# ignitors.net
KiCad netlist of a schematic drawn in EAGLE
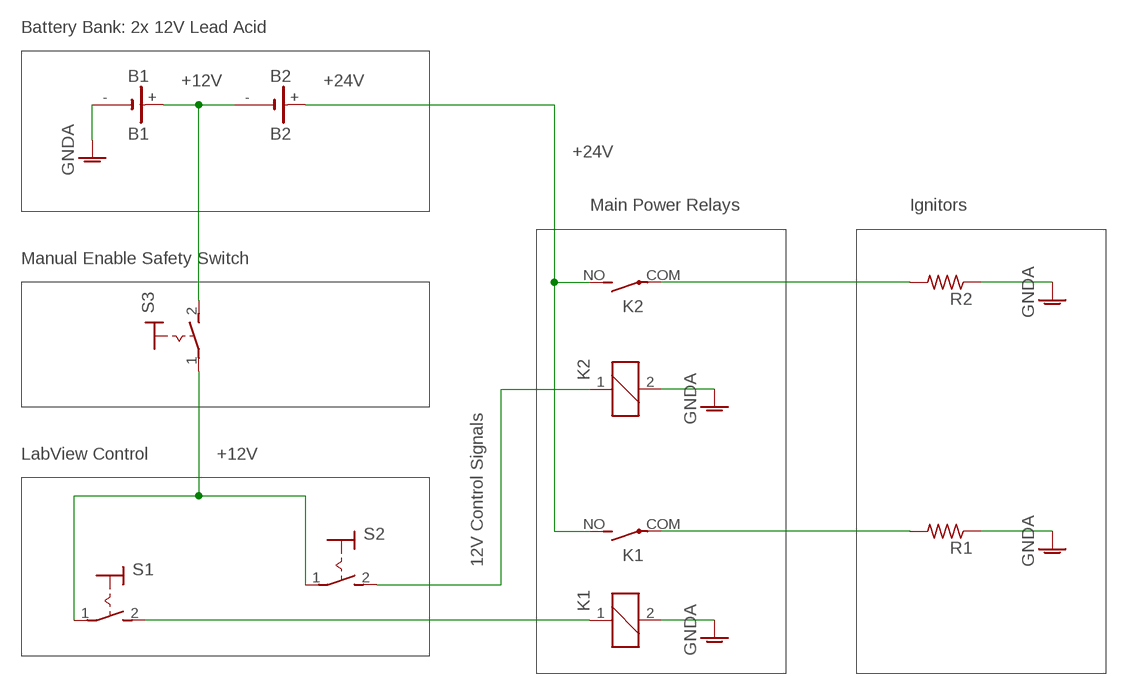
[diagram p0: schematic, sheet 1]

(export (version "E")
  (design (tool "Eeschema 10.0.6"))
  (components
    (comp (ref "B1")
      (value "B1")
      (footprint "eagle-import:SL-160AA_PT")
      (libsource (lib "eagle-import") (part "SL-160AA/PT"))
    )
    (comp (ref "B2")
      (value "B2")
      (footprint "eagle-import:SL-160AA_PT")
      (libsource (lib "eagle-import") (part "SL-160AA/PT"))
    )
    (comp (ref "K1")
      (value "APF30212A")
      (footprint "eagle-import:APF30212A")
      (libsource (lib "eagle-import") (part "APF30212A"))
    )
    (comp (ref "K2")
      (value "APF30212A")
      (footprint "eagle-import:APF30212A")
      (libsource (lib "eagle-import") (part "APF30212A"))
    )
    (comp (ref "R1")
      (value "R-US_0204/2V")
      (footprint "eagle-import:0204V")
      (libsource (lib "eagle-import") (part "R-US_0204/2V"))
    )
    (comp (ref "R2")
      (value "R-US_0204/2V")
      (footprint "eagle-import:0204V")
      (libsource (lib "eagle-import") (part "R-US_0204/2V"))
    )
    (comp (ref "S1")
      (value "MS243")
      (footprint "eagle-import:MS243")
      (libsource (lib "eagle-import") (part "MS243"))
    )
    (comp (ref "S2")
      (value "MS243")
      (footprint "eagle-import:MS243")
      (libsource (lib "eagle-import") (part "MS243"))
    )
    (comp (ref "S3")
      (value "MS243")
      (footprint "eagle-import:MS243")
      (libsource (lib "eagle-import") (part "MS243"))
    )
  )
  (nets
    (net (code "1") (name "GNDA") (class "Default")
      (node (ref "B1") (pin "-") (pinfunction "-_-") (pintype "passive"))
      (node (ref "K1") (pin "2") (pinfunction "2_2") (pintype "passive"))
      (node (ref "K2") (pin "2") (pinfunction "2_2") (pintype "passive"))
      (node (ref "R1") (pin "1") (pinfunction "1_1") (pintype "passive"))
      (node (ref "R2") (pin "1") (pinfunction "1_1") (pintype "passive"))
    )
    (net (code "2") (name "Net-(K1B-P)") (class "Default")
      (node (ref "K1") (pin "COM") (pinfunction "P_COM") (pintype "passive"))
      (node (ref "R1") (pin "2") (pinfunction "2_2") (pintype "passive"))
    )
    (net (code "3") (name "Net-(K1B-S)") (class "Default")
      (node (ref "B2") (pin "+") (pinfunction "+_+") (pintype "passive"))
      (node (ref "K1") (pin "NO") (pinfunction "S_NO") (pintype "passive"))
      (node (ref "K2") (pin "NO") (pinfunction "S_NO") (pintype "passive"))
    )
    (net (code "4") (name "Net-(K2B-P)") (class "Default")
      (node (ref "K2") (pin "COM") (pinfunction "P_COM") (pintype "passive"))
      (node (ref "R2") (pin "2") (pinfunction "2_2") (pintype "passive"))
    )
    (net (code "5") (name "Net-(S1-P)") (class "Default")
      (node (ref "S1") (pin "1") (pinfunction "P_1") (pintype "passive"))
      (node (ref "S2") (pin "1") (pinfunction "P_1") (pintype "passive"))
      (node (ref "S3") (pin "1") (pinfunction "P_1") (pintype "passive"))
    )
    (net (code "6") (name "Net-(S1-S)") (class "Default")
      (node (ref "K1") (pin "1") (pinfunction "1_1") (pintype "passive"))
      (node (ref "S1") (pin "2") (pinfunction "S_2") (pintype "passive"))
    )
    (net (code "7") (name "Net-(S2-S)") (class "Default")
      (node (ref "K2") (pin "1") (pinfunction "1_1") (pintype "passive"))
      (node (ref "S2") (pin "2") (pinfunction "S_2") (pintype "passive"))
    )
    (net (code "8") (name "Net-(S3-S)") (class "Default")
      (node (ref "B1") (pin "+") (pinfunction "+_+") (pintype "passive"))
      (node (ref "B2") (pin "-") (pinfunction "-_-") (pintype "passive"))
      (node (ref "S3") (pin "2") (pinfunction "S_2") (pintype "passive"))
    )
    (net (code "9") (name "unconnected-(B1---Pad-@1)") (class "Default")
      (node (ref "B1") (pin "-@1") (pinfunction "-_-@1") (pintype "passive"))
    )
    (net (code "10") (name "unconnected-(B2---Pad-@1)") (class "Default")
      (node (ref "B2") (pin "-@1") (pinfunction "-_-@1") (pintype "passive"))
    )
  )
)
